# OpenTag3.net
KiCad netlist of a schematic drawn in Altium Designer
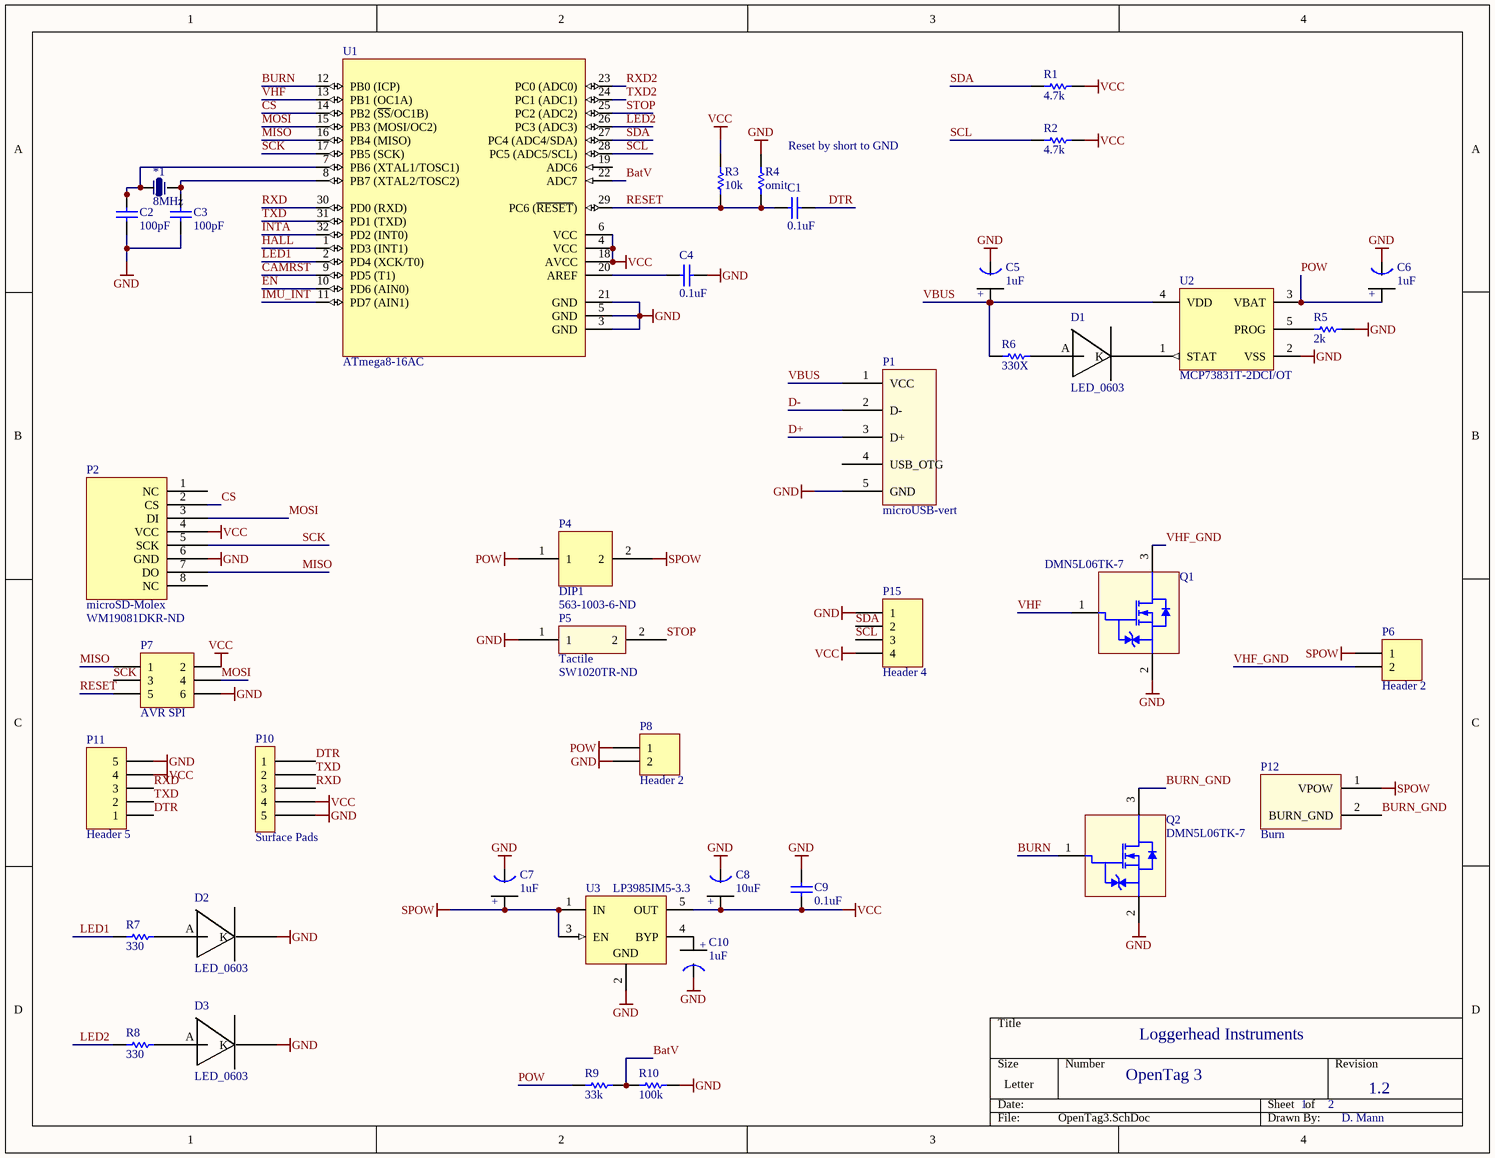
[diagram p0: OpenTag3.SchDoc]

(export (version "E")
  (design (tool "Eeschema 10.0.6"))
  (components
    (comp (ref "*1") (value "8MHz") (footprint "XTAL-ABM3") (libsource (lib "Loggerhead") (part "XTAL-ABM3")))
    (comp (ref "C1")
      (value "0.1uF")
      (footprint "0402")
      (description "Ceramic Chip Capacitor - Standard")
      (fields (field (name "PUBLISHER") "Altium Limited"))
      (libsource (lib "KEMET Chip Capacitor") (part "C0402"))
    )
    (comp (ref "C2")
      (value "100pF")
      (footprint "0402")
      (description "Ceramic Chip Capacitor - Standard")
      (fields (field (name "PUBLISHER") "Altium Limited"))
      (libsource (lib "KEMET Chip Capacitor") (part "C0402"))
    )
    (comp (ref "C3")
      (value "100pF")
      (footprint "0402")
      (description "Ceramic Chip Capacitor - Standard")
      (fields (field (name "PUBLISHER") "Altium Limited"))
      (libsource (lib "KEMET Chip Capacitor") (part "C0402"))
    )
    (comp (ref "C4")
      (value "0.1uF")
      (footprint "0402")
      (description "Ceramic Chip Capacitor - Standard")
      (fields (field (name "PUBLISHER") "Altium Limited"))
      (libsource (lib "KEMET Chip Capacitor") (part "C0402"))
    )
    (comp (ref "C5") (value "1uF") (footprint "Tant0805") (libsource (lib "Loggerhead") (part "Tant0805")))
    (comp (ref "C6") (value "1uF") (footprint "Tant0805") (libsource (lib "Loggerhead") (part "Tant0805")))
    (comp (ref "C7") (value "1uF") (footprint "Tant0805") (libsource (lib "Loggerhead") (part "Tant0805")))
    (comp (ref "C8") (value "10uF") (footprint "Tant0805") (libsource (lib "Loggerhead") (part "Tant0805")))
    (comp (ref "C9")
      (value "0.1uF")
      (footprint "0402")
      (description "Ceramic Chip Capacitor - Standard")
      (fields (field (name "PUBLISHER") "Altium Limited"))
      (libsource (lib "KEMET Chip Capacitor") (part "C0402"))
    )
    (comp (ref "C10") (value "1uF") (footprint "Tant0805") (libsource (lib "Loggerhead") (part "Tant0805")))
    (comp (ref "D1")
      (value "LED_0603")
      (footprint "Diode0603")
      (libsource (lib "Loggerhead") (part "LED_0603"))
    )
    (comp (ref "D2")
      (value "LED_0603")
      (footprint "Diode0603")
      (libsource (lib "Loggerhead") (part "LED_0603"))
    )
    (comp (ref "D3")
      (value "LED_0603")
      (footprint "Diode0603")
      (libsource (lib "Loggerhead") (part "LED_0603"))
    )
    (comp (ref "P1")
      (value "microUSB-vert")
      (footprint "MICROUSB-VERT")
      (description "Molex 105133-0011")
      (libsource (lib "Loggerhead") (part "microUSB-vert"))
    )
    (comp (ref "P2")
      (value "microSD-Molex")
      (footprint "microSD_Molex_hinged")
      (fields (field (name "SUPPLIER PART NUMBER 1") "WM19081DKR-ND"))
      (libsource (lib "Loggerhead") (part "microSD_Molex_hinged"))
    )
    (comp (ref "P4")
      (value "DIP1")
      (footprint "DIP1")
      (fields (field (name "SUPPLIER PART NUMBER 1") "563-1003-6-ND"))
      (libsource (lib "Loggerhead") (part "DIP1"))
    )
    (comp (ref "P5")
      (value "Tactile")
      (footprint "Tactile-B3U-1000")
      (fields (field (name "SUPPLIER PART NUMBER 1") "SW1020TR-ND"))
      (libsource (lib "Loggerhead") (part "Tactile_B3U-1000"))
    )
    (comp (ref "P6")
      (value "Header 2")
      (footprint "HDR1X2")
      (description "Header, 2-Pin")
      (fields (field (name "PUBLISHER") "Altium Limited"))
      (libsource (lib "Miscellaneous Connectors") (part "Header 2"))
    )
    (comp (ref "P7")
      (value "AVR SPI")
      (footprint "HDR2X3")
      (description "Header, 3-Pin, Dual row")
      (fields (field (name "PUBLISHER") "Altium Limited"))
      (libsource (lib "Miscellaneous Connectors") (part "Header 3X2"))
    )
    (comp (ref "P8")
      (value "Header 2")
      (footprint "HDR1X2")
      (description "Header, 2-Pin")
      (fields (field (name "PUBLISHER") "Altium Limited"))
      (libsource (lib "Miscellaneous Connectors") (part "Header 2"))
    )
    (comp (ref "P10")
      (value "Surface Pads")
      (footprint "Surface Pads 5 x 2mm")
      (libsource (lib "Loggerhead") (part "SurfacePads 5x2mm"))
    )
    (comp (ref "P11")
      (value "Header 5")
      (footprint "HDR1X5")
      (description "Header, 5-Pin")
      (fields (field (name "PUBLISHER") "Altium Limited"))
      (libsource (lib "Miscellaneous Connectors") (part "Header 5"))
    )
    (comp (ref "P12") (value "Burn") (footprint "BURN") (libsource (lib "Loggerhead") (part "Burn Screw")))
    (comp (ref "P15")
      (value "Header 4")
      (footprint "HDR1X4")
      (description "Header, 4-Pin")
      (fields (field (name "PUBLISHER") "Altium Limited"))
      (libsource (lib "Miscellaneous Connectors") (part "Header 4"))
    )
    (comp (ref "Q1")
      (value "DMN5L06TK-7")
      (footprint "SOT-523")
      (description "Ultra-low leakage Enhanced MOSFET")
      (fields
        (field (name "CREATOR AND DATE") "Will Flanery 2010-09-02")
        (field (name "FOOTPRINT VERIFIED BY") "*")
        (field (name "SCHEMATIC VERIFIED BY") "*")
        (field (name "VENDOR INFO VERIFIED BY") "*")
      )
      (libsource (lib "Flanery") (part "FET DMN5L06TK-7"))
    )
    (comp (ref "Q2")
      (value "DMN5L06TK-7")
      (footprint "SOT-523")
      (description "Ultra-low leakage Enhanced MOSFET")
      (fields
        (field (name "CREATOR AND DATE") "Will Flanery 2010-09-02")
        (field (name "FOOTPRINT VERIFIED BY") "*")
        (field (name "SCHEMATIC VERIFIED BY") "*")
        (field (name "VENDOR INFO VERIFIED BY") "*")
      )
      (libsource (lib "Flanery") (part "FET DMN5L06TK-7"))
    )
    (comp (ref "R1")
      (value "4.7k")
      (footprint "3-0603")
      (fields (field (name "PUBLISHER") "Altium Limited"))
      (libsource (lib "Panasonic Resistor") (part "ERJ3RK"))
    )
    (comp (ref "R2")
      (value "4.7k")
      (footprint "3-0603")
      (fields (field (name "PUBLISHER") "Altium Limited"))
      (libsource (lib "Panasonic Resistor") (part "ERJ3RK"))
    )
    (comp (ref "R3")
      (value "10k")
      (footprint "3-0603")
      (fields (field (name "PUBLISHER") "Altium Limited"))
      (libsource (lib "Panasonic Resistor") (part "ERJ3RK"))
    )
    (comp (ref "R4")
      (value "omit")
      (footprint "3-0603")
      (fields (field (name "PUBLISHER") "Altium Limited"))
      (libsource (lib "Panasonic Resistor") (part "ERJ3RK"))
    )
    (comp (ref "R5")
      (value "2k")
      (footprint "3-0603")
      (fields (field (name "PUBLISHER") "Altium Limited"))
      (libsource (lib "Panasonic Resistor") (part "ERJ3RK"))
    )
    (comp (ref "R6")
      (value "330X")
      (footprint "3-0603")
      (fields (field (name "PUBLISHER") "Altium Limited"))
      (libsource (lib "Panasonic Resistor") (part "ERJ3RK"))
    )
    (comp (ref "R7")
      (value "330")
      (footprint "3-0603")
      (fields (field (name "PUBLISHER") "Altium Limited"))
      (libsource (lib "Panasonic Resistor") (part "ERJ3RK"))
    )
    (comp (ref "R8")
      (value "330")
      (footprint "3-0603")
      (fields (field (name "PUBLISHER") "Altium Limited"))
      (libsource (lib "Panasonic Resistor") (part "ERJ3RK"))
    )
    (comp (ref "R9")
      (value "33k")
      (footprint "3-0603")
      (fields (field (name "PUBLISHER") "Altium Limited"))
      (libsource (lib "Panasonic Resistor") (part "ERJ3RK"))
    )
    (comp (ref "R10")
      (value "100k")
      (footprint "3-0603")
      (fields (field (name "PUBLISHER") "Altium Limited"))
      (libsource (lib "Panasonic Resistor") (part "ERJ3RK"))
    )
    (comp (ref "U1")
      (value "ATmega8-16AC")
      (footprint "32M1-A_M")
      (description "8-Bit AVR Microcontroller with 8K Bytes of In-System Programmable Flash Memory")
      (fields (field (name "PUBLISHER") "Altium Limited"))
      (libsource (lib "Atmel Microcontroller 8-Bit AVR") (part "ATmega8-16AC"))
    )
    (comp (ref "U2")
      (value "MCP73831T-2DCI/OT")
      (footprint "SOT-23-OT5_N")
      (libsource (lib "Microchip Power Management Battery Management") (part "MCP73831T-2DCI/OT"))
    )
    (comp (ref "U3")
      (value "LP3985IM5-3.3")
      (footprint "MF05A_N")
      (description "Micropower, 150mA Low-Noise Ultra Low-Dropout CMOS Voltage Regulator")
      (fields
        (field (name "MANUFACTURER") "National Semiconductor")
        (field (name "DIGIKEYPARTNUMBER") "LP3985IM5-3.3CT-ND")
        (field (name "PUBLISHER") "Altium Limited")
      )
      (libsource (lib "NSC LDO") (part "LP3985IM5-3.3"))
    )
  )
  (nets
    (net (code "1") (name "/BURN") (class "Default")
      (node (ref "Q2") (pin "1") (pinfunction "G_1") (pintype "passive"))
      (node (ref "U1") (pin "12") (pinfunction "PB0_(ICP)_12") (pintype "bidirectional"))
    )
    (net (code "2") (name "/BURN_GND") (class "Default")
      (node (ref "P12") (pin "2") (pinfunction "BURN_GND_2") (pintype "passive"))
      (node (ref "Q2") (pin "3") (pinfunction "D_3") (pintype "passive"))
    )
    (net (code "3") (name "/BatV") (class "Default")
      (node (ref "R10") (pin "2") (pinfunction "2_2") (pintype "passive"))
      (node (ref "R9") (pin "1") (pinfunction "1_1") (pintype "passive"))
      (node (ref "U1") (pin "22") (pinfunction "ADC7_22") (pintype "input"))
    )
    (net (code "4") (name "/CAMRST") (class "Default")
      (node (ref "U1") (pin "9") (pinfunction "PD5_(T1)_9") (pintype "bidirectional"))
    )
    (net (code "5") (name "/CS") (class "Default")
      (node (ref "P2") (pin "2") (pinfunction "CS_2") (pintype "passive"))
      (node (ref "U1") (pin "14") (pinfunction "PB2_(~{SS}/OC1B)_14") (pintype "bidirectional"))
    )
    (net (code "6") (name "/D+") (class "Default")
      (node (ref "P1") (pin "3") (pinfunction "D+_3") (pintype "passive"))
    )
    (net (code "7") (name "/D-") (class "Default")
      (node (ref "P1") (pin "2") (pinfunction "D-_2") (pintype "passive"))
    )
    (net (code "8") (name "/DTR") (class "Default")
      (node (ref "C1") (pin "2") (pinfunction "2_2") (pintype "passive"))
      (node (ref "P10") (pin "1") (pinfunction "1_1") (pintype "passive"))
      (node (ref "P11") (pin "1") (pinfunction "1_1") (pintype "passive"))
    )
    (net (code "9") (name "/EN") (class "Default")
      (node (ref "U1") (pin "10") (pinfunction "PD6_(AIN0)_10") (pintype "bidirectional"))
    )
    (net (code "10") (name "/HALL") (class "Default")
      (node (ref "U1") (pin "1") (pinfunction "PD3_(INT1)_1") (pintype "bidirectional"))
    )
    (net (code "11") (name "/IMU_INT") (class "Default")
      (node (ref "U1") (pin "11") (pinfunction "PD7_(AIN1)_11") (pintype "bidirectional"))
    )
    (net (code "12") (name "/INTA") (class "Default")
      (node (ref "U1") (pin "32") (pinfunction "PD2_(INT0)_32") (pintype "bidirectional"))
    )
    (net (code "13") (name "/LED1") (class "Default")
      (node (ref "R7") (pin "1") (pinfunction "1_1") (pintype "passive"))
      (node (ref "U1") (pin "2") (pinfunction "PD4_(XCK/T0)_2") (pintype "bidirectional"))
    )
    (net (code "14") (name "/LED2") (class "Default")
      (node (ref "R8") (pin "1") (pinfunction "1_1") (pintype "passive"))
      (node (ref "U1") (pin "26") (pinfunction "PC3_(ADC3)_26") (pintype "bidirectional"))
    )
    (net (code "15") (name "/MISO") (class "Default")
      (node (ref "P2") (pin "7") (pinfunction "DO_7") (pintype "passive"))
      (node (ref "P7") (pin "1") (pinfunction "1_1") (pintype "passive"))
      (node (ref "U1") (pin "16") (pinfunction "PB4_(MISO)_16") (pintype "bidirectional"))
    )
    (net (code "16") (name "/MOSI") (class "Default")
      (node (ref "P2") (pin "3") (pinfunction "DI_3") (pintype "passive"))
      (node (ref "P7") (pin "4") (pinfunction "4_4") (pintype "passive"))
      (node (ref "U1") (pin "15") (pinfunction "PB3_(MOSI/OC2)_15") (pintype "bidirectional"))
    )
    (net (code "17") (name "/RESET") (class "Default")
      (node (ref "C1") (pin "1") (pinfunction "1_1") (pintype "passive"))
      (node (ref "P7") (pin "5") (pinfunction "5_5") (pintype "passive"))
      (node (ref "R3") (pin "1") (pinfunction "1_1") (pintype "passive"))
      (node (ref "R4") (pin "1") (pinfunction "1_1") (pintype "passive"))
      (node (ref "U1") (pin "29") (pinfunction "PC6_(~{RESET})_29") (pintype "bidirectional"))
    )
    (net (code "18") (name "/RXD") (class "Default")
      (node (ref "P10") (pin "3") (pinfunction "3_3") (pintype "passive"))
      (node (ref "P11") (pin "3") (pinfunction "3_3") (pintype "passive"))
      (node (ref "U1") (pin "30") (pinfunction "PD0_(RXD)_30") (pintype "bidirectional"))
    )
    (net (code "19") (name "/RXD2") (class "Default")
      (node (ref "U1") (pin "23") (pinfunction "PC0_(ADC0)_23") (pintype "bidirectional"))
    )
    (net (code "20") (name "/SCK") (class "Default")
      (node (ref "P2") (pin "5") (pinfunction "SCK_5") (pintype "passive"))
      (node (ref "P7") (pin "3") (pinfunction "3_3") (pintype "passive"))
      (node (ref "U1") (pin "17") (pinfunction "PB5_(SCK)_17") (pintype "bidirectional"))
    )
    (net (code "21") (name "/SCL") (class "Default")
      (node (ref "P15") (pin "3") (pinfunction "3_3") (pintype "passive"))
      (node (ref "R2") (pin "1") (pinfunction "1_1") (pintype "passive"))
      (node (ref "U1") (pin "28") (pinfunction "PC5_(ADC5/SCL)_28") (pintype "bidirectional"))
    )
    (net (code "22") (name "/SDA") (class "Default")
      (node (ref "P15") (pin "2") (pinfunction "2_2") (pintype "passive"))
      (node (ref "R1") (pin "1") (pinfunction "1_1") (pintype "passive"))
      (node (ref "U1") (pin "27") (pinfunction "PC4_(ADC4/SDA)_27") (pintype "bidirectional"))
    )
    (net (code "23") (name "/STOP") (class "Default")
      (node (ref "P5") (pin "2") (pinfunction "2_2") (pintype "passive"))
      (node (ref "U1") (pin "25") (pinfunction "PC2_(ADC2)_25") (pintype "bidirectional"))
    )
    (net (code "24") (name "/TXD") (class "Default")
      (node (ref "P10") (pin "2") (pinfunction "2_2") (pintype "passive"))
      (node (ref "P11") (pin "2") (pinfunction "2_2") (pintype "passive"))
      (node (ref "U1") (pin "31") (pinfunction "PD1_(TXD)_31") (pintype "bidirectional"))
    )
    (net (code "25") (name "/TXD2") (class "Default")
      (node (ref "U1") (pin "24") (pinfunction "PC1_(ADC1)_24") (pintype "bidirectional"))
    )
    (net (code "26") (name "/VBUS") (class "Default")
      (node (ref "C5") (pin "2") (pinfunction "+_2") (pintype "passive"))
      (node (ref "P1") (pin "1") (pinfunction "VCC_1") (pintype "passive"))
      (node (ref "R6") (pin "1") (pinfunction "1_1") (pintype "passive"))
      (node (ref "U2") (pin "4") (pinfunction "VDD_4") (pintype "power_in"))
    )
    (net (code "27") (name "/VHF") (class "Default")
      (node (ref "Q1") (pin "1") (pinfunction "G_1") (pintype "passive"))
      (node (ref "U1") (pin "13") (pinfunction "PB1_(OC1A)_13") (pintype "bidirectional"))
    )
    (net (code "28") (name "/VHF_GND") (class "Default")
      (node (ref "P6") (pin "2") (pinfunction "2_2") (pintype "passive"))
      (node (ref "Q1") (pin "3") (pinfunction "D_3") (pintype "passive"))
    )
    (net (code "29") (name "GND") (class "Default")
      (node (ref "C10") (pin "1") (pinfunction "GND_1") (pintype "passive"))
      (node (ref "C2") (pin "1") (pinfunction "1_1") (pintype "passive"))
      (node (ref "C3") (pin "1") (pinfunction "1_1") (pintype "passive"))
      (node (ref "C4") (pin "2") (pinfunction "2_2") (pintype "passive"))
      (node (ref "C5") (pin "1") (pinfunction "GND_1") (pintype "passive"))
      (node (ref "C6") (pin "1") (pinfunction "GND_1") (pintype "passive"))
      (node (ref "C7") (pin "1") (pinfunction "GND_1") (pintype "passive"))
      (node (ref "C8") (pin "1") (pinfunction "GND_1") (pintype "passive"))
      (node (ref "C9") (pin "2") (pinfunction "2_2") (pintype "passive"))
      (node (ref "D2") (pin "K") (pinfunction "K_K") (pintype "passive"))
      (node (ref "D3") (pin "K") (pinfunction "K_K") (pintype "passive"))
      (node (ref "P1") (pin "5") (pinfunction "GND_5") (pintype "passive"))
      (node (ref "P10") (pin "5") (pinfunction "5_5") (pintype "passive"))
      (node (ref "P11") (pin "5") (pinfunction "5_5") (pintype "passive"))
      (node (ref "P15") (pin "1") (pinfunction "1_1") (pintype "passive"))
      (node (ref "P2") (pin "6") (pinfunction "GND_6") (pintype "passive"))
      (node (ref "P5") (pin "1") (pinfunction "1_1") (pintype "passive"))
      (node (ref "P7") (pin "6") (pinfunction "6_6") (pintype "passive"))
      (node (ref "P8") (pin "2") (pinfunction "2_2") (pintype "passive"))
      (node (ref "Q1") (pin "2") (pinfunction "S_2") (pintype "passive"))
      (node (ref "Q2") (pin "2") (pinfunction "S_2") (pintype "passive"))
      (node (ref "R10") (pin "1") (pinfunction "1_1") (pintype "passive"))
      (node (ref "R4") (pin "2") (pinfunction "2_2") (pintype "passive"))
      (node (ref "R5") (pin "1") (pinfunction "1_1") (pintype "passive"))
      (node (ref "U1") (pin "21") (pinfunction "GND_21") (pintype "power_in"))
      (node (ref "U1") (pin "3") (pinfunction "GND_3") (pintype "power_in"))
      (node (ref "U1") (pin "5") (pinfunction "GND_5") (pintype "power_in"))
      (node (ref "U2") (pin "2") (pinfunction "VSS_2") (pintype "power_in"))
      (node (ref "U3") (pin "2") (pinfunction "GND_2") (pintype "power_in"))
    )
    (net (code "30") (name "Net-(C10-+)") (class "Default")
      (node (ref "C10") (pin "2") (pinfunction "+_2") (pintype "passive"))
      (node (ref "U3") (pin "4") (pinfunction "BYP_4") (pintype "passive"))
    )
    (net (code "31") (name "Net-(D1-PadA)") (class "Default")
      (node (ref "D1") (pin "A") (pinfunction "A_A") (pintype "passive"))
      (node (ref "R6") (pin "2") (pinfunction "2_2") (pintype "passive"))
    )
    (net (code "32") (name "Net-(D2-PadA)") (class "Default")
      (node (ref "D2") (pin "A") (pinfunction "A_A") (pintype "passive"))
      (node (ref "R7") (pin "2") (pinfunction "2_2") (pintype "passive"))
    )
    (net (code "33") (name "Net-(D3-PadA)") (class "Default")
      (node (ref "D3") (pin "A") (pinfunction "A_A") (pintype "passive"))
      (node (ref "R8") (pin "2") (pinfunction "2_2") (pintype "passive"))
    )
    (net (code "34") (name "Net-(U1-AREF)") (class "Default")
      (node (ref "C4") (pin "1") (pinfunction "1_1") (pintype "passive"))
      (node (ref "U1") (pin "20") (pinfunction "AREF_20") (pintype "passive"))
    )
    (net (code "35") (name "Net-(U1-PB6_(XTAL1{slash}TOSC1))") (class "Default")
      (node (ref "*1") (pin "1") (pinfunction "1_1") (pintype "passive"))
      (node (ref "C2") (pin "2") (pinfunction "2_2") (pintype "passive"))
      (node (ref "U1") (pin "7") (pinfunction "PB6_(XTAL1/TOSC1)_7") (pintype "bidirectional"))
    )
    (net (code "36") (name "Net-(U1-PB7_(XTAL2{slash}TOSC2))") (class "Default")
      (node (ref "*1") (pin "2") (pinfunction "2_2") (pintype "passive"))
      (node (ref "C3") (pin "2") (pinfunction "2_2") (pintype "passive"))
      (node (ref "U1") (pin "8") (pinfunction "PB7_(XTAL2/TOSC2)_8") (pintype "bidirectional"))
    )
    (net (code "37") (name "Net-(U2-PROG)") (class "Default")
      (node (ref "R5") (pin "2") (pinfunction "2_2") (pintype "passive"))
      (node (ref "U2") (pin "5") (pinfunction "PROG_5") (pintype "passive"))
    )
    (net (code "38") (name "Net-(U2-STAT)") (class "Default")
      (node (ref "D1") (pin "K") (pinfunction "K_K") (pintype "passive"))
      (node (ref "U2") (pin "1") (pinfunction "STAT_1") (pintype "output"))
    )
    (net (code "39") (name "POW") (class "Default")
      (node (ref "C6") (pin "2") (pinfunction "+_2") (pintype "passive"))
      (node (ref "P4") (pin "1") (pinfunction "1_1") (pintype "passive"))
      (node (ref "P8") (pin "1") (pinfunction "1_1") (pintype "passive"))
      (node (ref "R9") (pin "2") (pinfunction "2_2") (pintype "passive"))
      (node (ref "U2") (pin "3") (pinfunction "VBAT_3") (pintype "power_in"))
    )
    (net (code "40") (name "SPOW") (class "Default")
      (node (ref "C7") (pin "2") (pinfunction "+_2") (pintype "passive"))
      (node (ref "P12") (pin "1") (pinfunction "VPOW_1") (pintype "passive"))
      (node (ref "P4") (pin "2") (pinfunction "2_2") (pintype "passive"))
      (node (ref "P6") (pin "1") (pinfunction "1_1") (pintype "passive"))
      (node (ref "U3") (pin "1") (pinfunction "IN_1") (pintype "power_in"))
      (node (ref "U3") (pin "3") (pinfunction "EN_3") (pintype "input"))
    )
    (net (code "41") (name "VCC") (class "Default")
      (node (ref "C8") (pin "2") (pinfunction "+_2") (pintype "passive"))
      (node (ref "C9") (pin "1") (pinfunction "1_1") (pintype "passive"))
      (node (ref "P10") (pin "4") (pinfunction "4_4") (pintype "passive"))
      (node (ref "P11") (pin "4") (pinfunction "4_4") (pintype "passive"))
      (node (ref "P15") (pin "4") (pinfunction "4_4") (pintype "passive"))
      (node (ref "P2") (pin "4") (pinfunction "VCC_4") (pintype "passive"))
      (node (ref "P7") (pin "2") (pinfunction "2_2") (pintype "passive"))
      (node (ref "R1") (pin "2") (pinfunction "2_2") (pintype "passive"))
      (node (ref "R2") (pin "2") (pinfunction "2_2") (pintype "passive"))
      (node (ref "R3") (pin "2") (pinfunction "2_2") (pintype "passive"))
      (node (ref "U1") (pin "18") (pinfunction "AVCC_18") (pintype "power_in"))
      (node (ref "U1") (pin "4") (pinfunction "VCC_4") (pintype "power_in"))
      (node (ref "U1") (pin "6") (pinfunction "VCC_6") (pintype "power_in"))
      (node (ref "U3") (pin "5") (pinfunction "OUT_5") (pintype "power_in"))
    )
    (net (code "42") (name "unconnected-(P1-USB_OTG-Pad4)") (class "Default")
      (node (ref "P1") (pin "4") (pinfunction "USB_OTG_4") (pintype "passive"))
    )
    (net (code "43") (name "unconnected-(P2-NC-Pad1)") (class "Default")
      (node (ref "P2") (pin "1") (pinfunction "NC_1") (pintype "passive"))
    )
    (net (code "44") (name "unconnected-(P2-NC-Pad8)") (class "Default")
      (node (ref "P2") (pin "8") (pinfunction "NC_8") (pintype "passive"))
    )
    (net (code "45") (name "unconnected-(U1-ADC6-Pad19)") (class "Default")
      (node (ref "U1") (pin "19") (pinfunction "ADC6_19") (pintype "input"))
    )
  )
)
